# Intsy_128ch_20190417.net
KiCad netlist of a schematic drawn in EAGLE
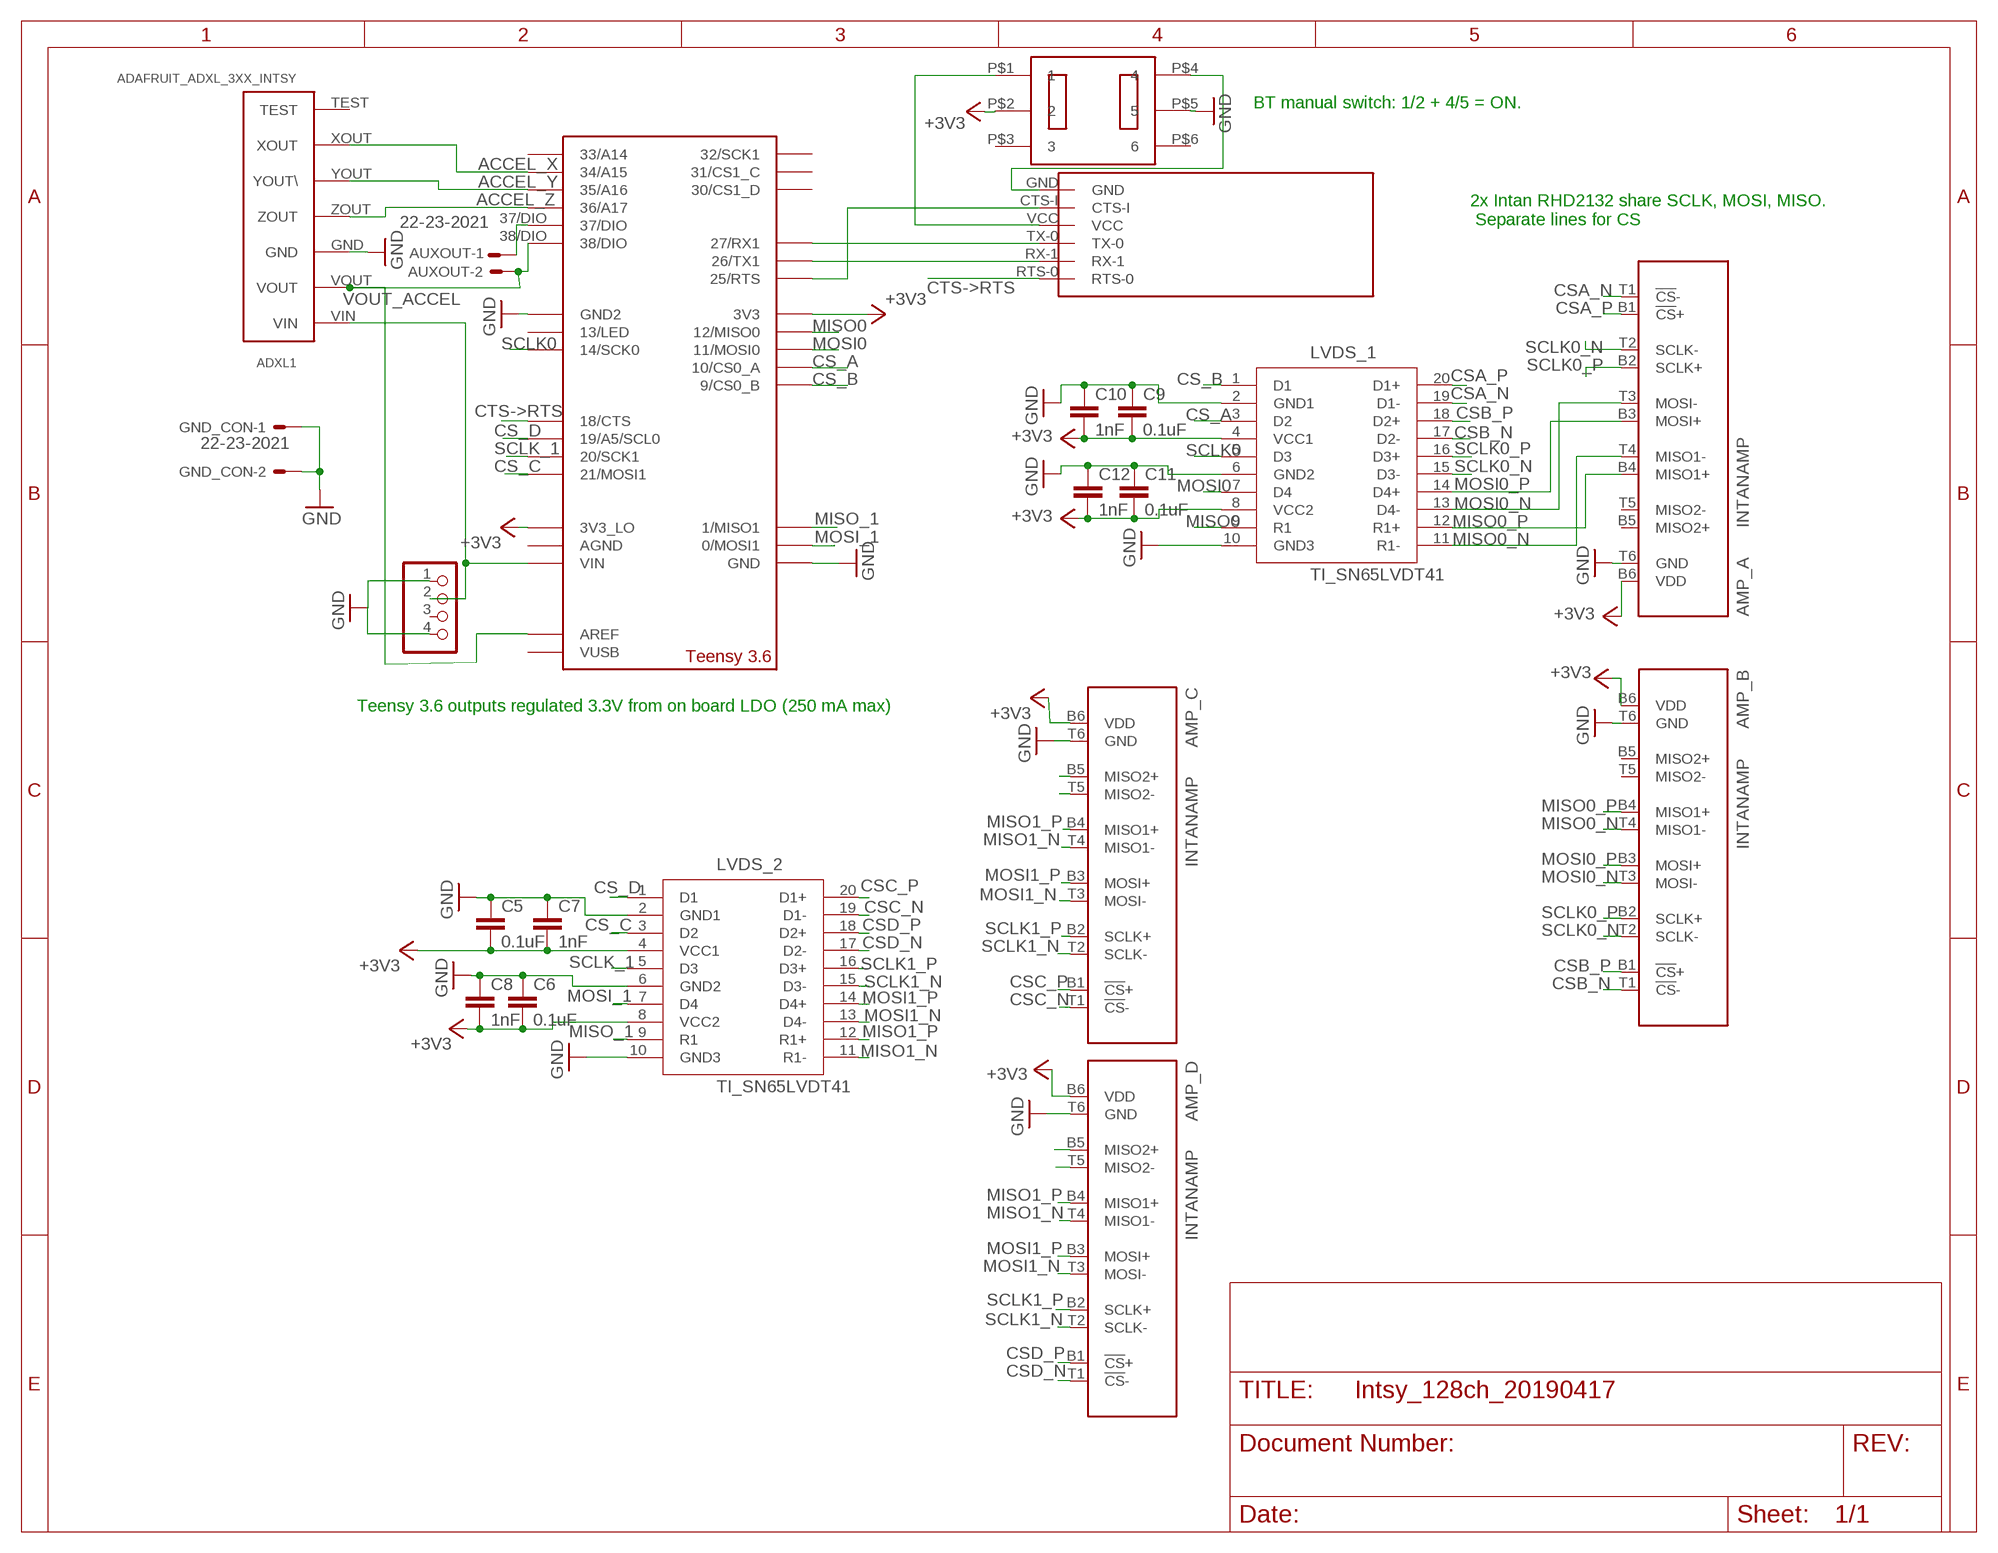
[diagram p0: schematic, sheet 1]

(export (version "E")
  (design (tool "Eeschema 10.0.6"))
  (components
    (comp (ref "ADXL1")
      (value "ADAFRUIT_ADXL_3XX_INTSY")
      (footprint "eagle-import:ADAFRUIT_ADXL_3XX")
      (libsource (lib "eagle-import") (part "ADAFRUIT_ADXL_3XX_INTSY"))
    )
    (comp (ref "AMP_A")
      (value "INTANAMP")
      (footprint "eagle-import:AMPBOARD")
      (libsource (lib "eagle-import") (part "INTANAMP"))
    )
    (comp (ref "AMP_B")
      (value "INTANAMP")
      (footprint "eagle-import:AMPBOARD")
      (libsource (lib "eagle-import") (part "INTANAMP"))
    )
    (comp (ref "AMP_C")
      (value "INTANAMP")
      (footprint "eagle-import:AMPBOARD")
      (libsource (lib "eagle-import") (part "INTANAMP"))
    )
    (comp (ref "AMP_D")
      (value "INTANAMP")
      (footprint "eagle-import:AMPBOARD")
      (libsource (lib "eagle-import") (part "INTANAMP"))
    )
    (comp (ref "AUXOUT")
      (value "22-23-2021")
      (footprint "eagle-import:22-23-2021")
      (fields (field (name "MF") "MOLEX"))
      (libsource (lib "eagle-import") (part "22-23-2021"))
    )
    (comp (ref "C5")
      (value "0.1uF")
      (footprint "eagle-import:C2012")
      (libsource (lib "eagle-import") (part "CC2012"))
    )
    (comp (ref "C6")
      (value "0.1uF")
      (footprint "eagle-import:C2012")
      (libsource (lib "eagle-import") (part "CC2012"))
    )
    (comp (ref "C7")
      (value "1nF")
      (footprint "eagle-import:C2012")
      (libsource (lib "eagle-import") (part "CC2012"))
    )
    (comp (ref "C8")
      (value "1nF")
      (footprint "eagle-import:C2012")
      (libsource (lib "eagle-import") (part "CC2012"))
    )
    (comp (ref "C9")
      (value "0.1uF")
      (footprint "eagle-import:C2012")
      (libsource (lib "eagle-import") (part "CC2012"))
    )
    (comp (ref "C10")
      (value "1nF")
      (footprint "eagle-import:C2012")
      (libsource (lib "eagle-import") (part "CC2012"))
    )
    (comp (ref "C11")
      (value "0.1uF")
      (footprint "eagle-import:C2012")
      (libsource (lib "eagle-import") (part "CC2012"))
    )
    (comp (ref "C12")
      (value "1nF")
      (footprint "eagle-import:C2012")
      (libsource (lib "eagle-import") (part "CC2012"))
    )
    (comp (ref "DPDT_1")
      (value "DPDT_1")
      (footprint "eagle-import:SLIDE_SWITCH_DPDT_NIDEC")
      (libsource (lib "eagle-import") (part "SLIDE_SWITCH_DPDT_NIDEC"))
    )
    (comp (ref "GND_CON")
      (value "22-23-2021")
      (footprint "eagle-import:22-23-2021")
      (fields (field (name "MF") "MOLEX"))
      (libsource (lib "eagle-import") (part "22-23-2021"))
    )
    (comp (ref "LVDS_1")
      (value "TI_SN65LVDT41")
      (footprint "eagle-import:SN65LVDT41_TSSOP20")
      (libsource (lib "eagle-import") (part "TI_SN65LVDT41"))
    )
    (comp (ref "LVDS_2")
      (value "TI_SN65LVDT41")
      (footprint "eagle-import:SN65LVDT41_TSSOP20")
      (libsource (lib "eagle-import") (part "TI_SN65LVDT41"))
    )
    (comp (ref "RN42")
      (value "RN42")
      (footprint "eagle-import:RN42")
      (libsource (lib "eagle-import") (part "RN42"))
    )
    (comp (ref "SW1")
      (value "LiPoIn")
      (footprint "eagle-import:PADS-4")
      (libsource (lib "eagle-import") (part "PADS-4"))
    )
    (comp (ref "U$2")
      (value "TEENSY_3.5/3.6_SIMPLE")
      (footprint "eagle-import:TEENSY_3.5_3.6_SIMPLE")
      (libsource (lib "eagle-import") (part "TEENSY_3.5/3.6_SIMPLE"))
    )
  )
  (nets
    (net (code "1") (name "+3V3") (class "Default")
      (node (ref "AMP_A") (pin "B6") (pinfunction "VDD_B6") (pintype "bidirectional"))
      (node (ref "AMP_B") (pin "B6") (pinfunction "VDD_B6") (pintype "bidirectional"))
      (node (ref "AMP_C") (pin "B6") (pinfunction "VDD_B6") (pintype "bidirectional"))
      (node (ref "AMP_D") (pin "B6") (pinfunction "VDD_B6") (pintype "bidirectional"))
      (node (ref "C10") (pin "2") (pinfunction "2_2") (pintype "passive"))
      (node (ref "C11") (pin "2") (pinfunction "2_2") (pintype "passive"))
      (node (ref "C12") (pin "2") (pinfunction "2_2") (pintype "passive"))
      (node (ref "C5") (pin "2") (pinfunction "2_2") (pintype "passive"))
      (node (ref "C6") (pin "2") (pinfunction "2_2") (pintype "passive"))
      (node (ref "C7") (pin "2") (pinfunction "2_2") (pintype "passive"))
      (node (ref "C8") (pin "2") (pinfunction "2_2") (pintype "passive"))
      (node (ref "C9") (pin "2") (pinfunction "2_2") (pintype "passive"))
      (node (ref "DPDT_1") (pin "P$2") (pinfunction "2_P$2") (pintype "bidirectional"))
      (node (ref "LVDS_1") (pin "4") (pinfunction "VCC1_4") (pintype "power_in"))
      (node (ref "LVDS_1") (pin "8") (pinfunction "VCC2_8") (pintype "bidirectional"))
      (node (ref "LVDS_2") (pin "4") (pinfunction "VCC1_4") (pintype "power_in"))
      (node (ref "LVDS_2") (pin "8") (pinfunction "VCC2_8") (pintype "bidirectional"))
      (node (ref "U$2") (pin "3V3") (pinfunction "3V3_3V3") (pintype "bidirectional"))
      (node (ref "U$2") (pin "3V3_LO") (pinfunction "3V3_LO_3V3_LO") (pintype "bidirectional"))
    )
    (net (code "2") (name "/ACCEL_X") (class "Default")
      (node (ref "ADXL1") (pin "XOUT") (pinfunction "XOUT_XOUT") (pintype "bidirectional"))
      (node (ref "U$2") (pin "34/A15") (pinfunction "34/A15_34/A15") (pintype "input"))
    )
    (net (code "3") (name "/ACCEL_Y") (class "Default")
      (node (ref "ADXL1") (pin "YOUT") (pinfunction "YOUT\\_YOUT") (pintype "bidirectional"))
      (node (ref "U$2") (pin "35/A16") (pinfunction "35/A16_35/A16") (pintype "bidirectional"))
    )
    (net (code "4") (name "/ACCEL_Z") (class "Default")
      (node (ref "ADXL1") (pin "ZOUT") (pinfunction "ZOUT_ZOUT") (pintype "bidirectional"))
      (node (ref "U$2") (pin "36/A17") (pinfunction "36/A17_36/A17") (pintype "bidirectional"))
    )
    (net (code "5") (name "/CSA_N") (class "Default")
      (node (ref "AMP_A") (pin "T1") (pinfunction "~{CS}-_T1") (pintype "bidirectional"))
      (node (ref "LVDS_1") (pin "19") (pinfunction "D1-_19") (pintype "bidirectional"))
    )
    (net (code "6") (name "/CSA_P") (class "Default")
      (node (ref "AMP_A") (pin "B1") (pinfunction "~{CS}+_B1") (pintype "bidirectional"))
      (node (ref "LVDS_1") (pin "20") (pinfunction "D1+_20") (pintype "bidirectional"))
    )
    (net (code "7") (name "/CSB_N") (class "Default")
      (node (ref "AMP_B") (pin "T1") (pinfunction "~{CS}-_T1") (pintype "bidirectional"))
      (node (ref "LVDS_1") (pin "17") (pinfunction "D2-_17") (pintype "bidirectional"))
    )
    (net (code "8") (name "/CSB_P") (class "Default")
      (node (ref "AMP_B") (pin "B1") (pinfunction "~{CS}+_B1") (pintype "bidirectional"))
      (node (ref "LVDS_1") (pin "18") (pinfunction "D2+_18") (pintype "bidirectional"))
    )
    (net (code "9") (name "/CSC_N") (class "Default")
      (node (ref "AMP_C") (pin "T1") (pinfunction "~{CS}-_T1") (pintype "bidirectional"))
      (node (ref "LVDS_2") (pin "19") (pinfunction "D1-_19") (pintype "bidirectional"))
    )
    (net (code "10") (name "/CSC_P") (class "Default")
      (node (ref "AMP_C") (pin "B1") (pinfunction "~{CS}+_B1") (pintype "bidirectional"))
      (node (ref "LVDS_2") (pin "20") (pinfunction "D1+_20") (pintype "bidirectional"))
    )
    (net (code "11") (name "/CSD_N") (class "Default")
      (node (ref "AMP_D") (pin "T1") (pinfunction "~{CS}-_T1") (pintype "bidirectional"))
      (node (ref "LVDS_2") (pin "17") (pinfunction "D2-_17") (pintype "bidirectional"))
    )
    (net (code "12") (name "/CSD_P") (class "Default")
      (node (ref "AMP_D") (pin "B1") (pinfunction "~{CS}+_B1") (pintype "bidirectional"))
      (node (ref "LVDS_2") (pin "18") (pinfunction "D2+_18") (pintype "bidirectional"))
    )
    (net (code "13") (name "/CS_A") (class "Default")
      (node (ref "LVDS_1") (pin "3") (pinfunction "D2_3") (pintype "bidirectional"))
      (node (ref "U$2") (pin "10/CS") (pinfunction "10/CS0_A_10/CS") (pintype "bidirectional"))
    )
    (net (code "14") (name "/CS_B") (class "Default")
      (node (ref "LVDS_1") (pin "1") (pinfunction "D1_1") (pintype "bidirectional"))
      (node (ref "U$2") (pin "9/CS") (pinfunction "9/CS0_B_9/CS") (pintype "bidirectional"))
    )
    (net (code "15") (name "/CS_C") (class "Default")
      (node (ref "LVDS_2") (pin "3") (pinfunction "D2_3") (pintype "bidirectional"))
      (node (ref "U$2") (pin "21/CS0/MOSI1") (pinfunction "21/MOSI1_21/CS0/MOSI1") (pintype "bidirectional"))
    )
    (net (code "16") (name "/CS_D") (class "Default")
      (node (ref "LVDS_2") (pin "1") (pinfunction "D1_1") (pintype "bidirectional"))
      (node (ref "U$2") (pin "19/A5/SCL") (pinfunction "19/A5/SCL0_19/A5/SCL") (pintype "bidirectional"))
    )
    (net (code "17") (name "/CTS->RTS") (class "Default")
      (node (ref "RN42") (pin "RTS-0") (pinfunction "RTS-0_RTS-0") (pintype "bidirectional"))
      (node (ref "U$2") (pin "18/CTS") (pinfunction "18/CTS_18/CTS") (pintype "bidirectional"))
    )
    (net (code "18") (name "/MISO0") (class "Default")
      (node (ref "LVDS_1") (pin "9") (pinfunction "R1_9") (pintype "bidirectional"))
      (node (ref "U$2") (pin "12/MISO0") (pinfunction "12/MISO0_12/MISO0") (pintype "bidirectional"))
    )
    (net (code "19") (name "/MISO0_N") (class "Default")
      (node (ref "AMP_A") (pin "T4") (pinfunction "MISO1-_T4") (pintype "bidirectional"))
      (node (ref "AMP_B") (pin "T4") (pinfunction "MISO1-_T4") (pintype "bidirectional"))
      (node (ref "LVDS_1") (pin "11") (pinfunction "R1-_11") (pintype "bidirectional"))
    )
    (net (code "20") (name "/MISO0_P") (class "Default")
      (node (ref "AMP_A") (pin "B4") (pinfunction "MISO1+_B4") (pintype "bidirectional"))
      (node (ref "AMP_B") (pin "B4") (pinfunction "MISO1+_B4") (pintype "bidirectional"))
      (node (ref "LVDS_1") (pin "12") (pinfunction "R1+_12") (pintype "bidirectional"))
    )
    (net (code "21") (name "/MISO1_N") (class "Default")
      (node (ref "AMP_C") (pin "T4") (pinfunction "MISO1-_T4") (pintype "bidirectional"))
      (node (ref "AMP_D") (pin "T4") (pinfunction "MISO1-_T4") (pintype "bidirectional"))
      (node (ref "LVDS_2") (pin "11") (pinfunction "R1-_11") (pintype "bidirectional"))
    )
    (net (code "22") (name "/MISO1_P") (class "Default")
      (node (ref "AMP_C") (pin "B4") (pinfunction "MISO1+_B4") (pintype "bidirectional"))
      (node (ref "AMP_D") (pin "B4") (pinfunction "MISO1+_B4") (pintype "bidirectional"))
      (node (ref "LVDS_2") (pin "12") (pinfunction "R1+_12") (pintype "bidirectional"))
    )
    (net (code "23") (name "/MISO_1") (class "Default")
      (node (ref "LVDS_2") (pin "9") (pinfunction "R1_9") (pintype "bidirectional"))
      (node (ref "U$2") (pin "1/MISO1") (pinfunction "1/MISO1_1/MISO1") (pintype "bidirectional"))
    )
    (net (code "24") (name "/MOSI0") (class "Default")
      (node (ref "LVDS_1") (pin "7") (pinfunction "D4_7") (pintype "bidirectional"))
      (node (ref "U$2") (pin "11/MOSI0") (pinfunction "11/MOSI0_11/MOSI0") (pintype "bidirectional"))
    )
    (net (code "25") (name "/MOSI0_N") (class "Default")
      (node (ref "AMP_A") (pin "T3") (pinfunction "MOSI-_T3") (pintype "bidirectional"))
      (node (ref "AMP_B") (pin "T3") (pinfunction "MOSI-_T3") (pintype "bidirectional"))
      (node (ref "LVDS_1") (pin "13") (pinfunction "D4-_13") (pintype "bidirectional"))
    )
    (net (code "26") (name "/MOSI0_P") (class "Default")
      (node (ref "AMP_A") (pin "B3") (pinfunction "MOSI+_B3") (pintype "bidirectional"))
      (node (ref "AMP_B") (pin "B3") (pinfunction "MOSI+_B3") (pintype "bidirectional"))
      (node (ref "LVDS_1") (pin "14") (pinfunction "D4+_14") (pintype "bidirectional"))
    )
    (net (code "27") (name "/MOSI1_N") (class "Default")
      (node (ref "AMP_C") (pin "T3") (pinfunction "MOSI-_T3") (pintype "bidirectional"))
      (node (ref "AMP_D") (pin "T3") (pinfunction "MOSI-_T3") (pintype "bidirectional"))
      (node (ref "LVDS_2") (pin "13") (pinfunction "D4-_13") (pintype "bidirectional"))
    )
    (net (code "28") (name "/MOSI1_P") (class "Default")
      (node (ref "AMP_C") (pin "B3") (pinfunction "MOSI+_B3") (pintype "bidirectional"))
      (node (ref "AMP_D") (pin "B3") (pinfunction "MOSI+_B3") (pintype "bidirectional"))
      (node (ref "LVDS_2") (pin "14") (pinfunction "D4+_14") (pintype "bidirectional"))
    )
    (net (code "29") (name "/MOSI_1") (class "Default")
      (node (ref "LVDS_2") (pin "7") (pinfunction "D4_7") (pintype "bidirectional"))
      (node (ref "U$2") (pin "0/MOSI1") (pinfunction "0/MOSI1_0/MOSI1") (pintype "bidirectional"))
    )
    (net (code "30") (name "/SCLK0") (class "Default")
      (node (ref "LVDS_1") (pin "5") (pinfunction "D3_5") (pintype "bidirectional"))
      (node (ref "U$2") (pin "14/SCK0") (pinfunction "14/SCK0_14/SCK0") (pintype "bidirectional"))
    )
    (net (code "31") (name "/SCLK0_N") (class "Default")
      (node (ref "AMP_A") (pin "T2") (pinfunction "SCLK-_T2") (pintype "bidirectional"))
      (node (ref "AMP_B") (pin "T2") (pinfunction "SCLK-_T2") (pintype "bidirectional"))
      (node (ref "LVDS_1") (pin "15") (pinfunction "D3-_15") (pintype "bidirectional"))
    )
    (net (code "32") (name "/SCLK0_P") (class "Default")
      (node (ref "AMP_A") (pin "B2") (pinfunction "SCLK+_B2") (pintype "bidirectional"))
      (node (ref "AMP_B") (pin "B2") (pinfunction "SCLK+_B2") (pintype "bidirectional"))
      (node (ref "LVDS_1") (pin "16") (pinfunction "D3+_16") (pintype "bidirectional"))
    )
    (net (code "33") (name "/SCLK1_N") (class "Default")
      (node (ref "AMP_C") (pin "T2") (pinfunction "SCLK-_T2") (pintype "bidirectional"))
      (node (ref "AMP_D") (pin "T2") (pinfunction "SCLK-_T2") (pintype "bidirectional"))
      (node (ref "LVDS_2") (pin "15") (pinfunction "D3-_15") (pintype "bidirectional"))
    )
    (net (code "34") (name "/SCLK1_P") (class "Default")
      (node (ref "AMP_C") (pin "B2") (pinfunction "SCLK+_B2") (pintype "bidirectional"))
      (node (ref "AMP_D") (pin "B2") (pinfunction "SCLK+_B2") (pintype "bidirectional"))
      (node (ref "LVDS_2") (pin "16") (pinfunction "D3+_16") (pintype "bidirectional"))
    )
    (net (code "35") (name "/SCLK_1") (class "Default")
      (node (ref "LVDS_2") (pin "5") (pinfunction "D3_5") (pintype "bidirectional"))
      (node (ref "U$2") (pin "20/CS0/SCK1") (pinfunction "20/SCK1_20/CS0/SCK1") (pintype "bidirectional"))
    )
    (net (code "36") (name "/VOUT_ACCEL") (class "Default")
      (node (ref "ADXL1") (pin "VOUT") (pinfunction "VOUT_VOUT") (pintype "bidirectional"))
      (node (ref "AUXOUT") (pin "2") (pinfunction "S_2") (pintype "passive"))
      (node (ref "U$2") (pin "38/DIO") (pinfunction "38/DIO_38/DIO") (pintype "bidirectional"))
      (node (ref "U$2") (pin "AREF") (pinfunction "AREF_AREF") (pintype "bidirectional"))
    )
    (net (code "37") (name "GND") (class "Default")
      (node (ref "ADXL1") (pin "GND") (pinfunction "GND_GND") (pintype "power_in"))
      (node (ref "AMP_A") (pin "T6") (pinfunction "GND_T6") (pintype "power_in"))
      (node (ref "AMP_B") (pin "T6") (pinfunction "GND_T6") (pintype "power_in"))
      (node (ref "AMP_C") (pin "T6") (pinfunction "GND_T6") (pintype "power_in"))
      (node (ref "AMP_D") (pin "T6") (pinfunction "GND_T6") (pintype "power_in"))
      (node (ref "C10") (pin "1") (pinfunction "1_1") (pintype "passive"))
      (node (ref "C11") (pin "1") (pinfunction "1_1") (pintype "passive"))
      (node (ref "C12") (pin "1") (pinfunction "1_1") (pintype "passive"))
      (node (ref "C5") (pin "1") (pinfunction "1_1") (pintype "passive"))
      (node (ref "C6") (pin "1") (pinfunction "1_1") (pintype "passive"))
      (node (ref "C7") (pin "1") (pinfunction "1_1") (pintype "passive"))
      (node (ref "C8") (pin "1") (pinfunction "1_1") (pintype "passive"))
      (node (ref "C9") (pin "1") (pinfunction "1_1") (pintype "passive"))
      (node (ref "DPDT_1") (pin "P$5") (pinfunction "5_P$5") (pintype "bidirectional"))
      (node (ref "GND_CON") (pin "1") (pinfunction "S_1") (pintype "passive"))
      (node (ref "GND_CON") (pin "2") (pinfunction "S_2") (pintype "passive"))
      (node (ref "LVDS_1") (pin "10") (pinfunction "GND3_10") (pintype "power_in"))
      (node (ref "LVDS_1") (pin "2") (pinfunction "GND1_2") (pintype "power_in"))
      (node (ref "LVDS_1") (pin "6") (pinfunction "GND2_6") (pintype "power_in"))
      (node (ref "LVDS_2") (pin "10") (pinfunction "GND3_10") (pintype "power_in"))
      (node (ref "LVDS_2") (pin "2") (pinfunction "GND1_2") (pintype "power_in"))
      (node (ref "LVDS_2") (pin "6") (pinfunction "GND2_6") (pintype "power_in"))
      (node (ref "SW1") (pin "1") (pinfunction "1_1") (pintype "passive"))
      (node (ref "SW1") (pin "4") (pinfunction "4_4") (pintype "passive"))
      (node (ref "U$2") (pin "GND") (pinfunction "GND_GND") (pintype "bidirectional"))
      (node (ref "U$2") (pin "GND2") (pinfunction "GND2_GND2") (pintype "bidirectional"))
    )
    (net (code "38") (name "Net-(ADXL1-PadVIN)") (class "Default")
      (node (ref "ADXL1") (pin "VIN") (pinfunction "VIN_VIN") (pintype "power_in"))
      (node (ref "SW1") (pin "2") (pinfunction "2_2") (pintype "passive"))
      (node (ref "U$2") (pin "VIN") (pinfunction "VIN_VIN") (pintype "bidirectional"))
    )
    (net (code "39") (name "Net-(AUXOUTA-S)") (class "Default")
      (node (ref "AUXOUT") (pin "1") (pinfunction "S_1") (pintype "passive"))
      (node (ref "U$2") (pin "37/DIO") (pinfunction "37/DIO_37/DIO") (pintype "bidirectional"))
    )
    (net (code "40") (name "Net-(DPDT_1-1)") (class "Default")
      (node (ref "DPDT_1") (pin "P$1") (pinfunction "1_P$1") (pintype "bidirectional"))
      (node (ref "RN42") (pin "VCC") (pinfunction "VCC_VCC") (pintype "bidirectional"))
    )
    (net (code "41") (name "Net-(DPDT_1-4)") (class "Default")
      (node (ref "DPDT_1") (pin "P$4") (pinfunction "4_P$4") (pintype "bidirectional"))
      (node (ref "RN42") (pin "GND") (pinfunction "GND_GND") (pintype "bidirectional"))
    )
    (net (code "42") (name "Net-(RN42-PadCTS-I)") (class "Default")
      (node (ref "RN42") (pin "CTS-I") (pinfunction "CTS-I_CTS-I") (pintype "bidirectional"))
      (node (ref "U$2") (pin "25/RTS") (pinfunction "25/RTS_25/RTS") (pintype "bidirectional"))
    )
    (net (code "43") (name "Net-(RN42-PadRX-1)") (class "Default")
      (node (ref "RN42") (pin "RX-1") (pinfunction "RX-1_RX-1") (pintype "bidirectional"))
      (node (ref "U$2") (pin "26/TX1") (pinfunction "26/TX1_26/TX1") (pintype "bidirectional"))
    )
    (net (code "44") (name "Net-(RN42-PadTX-0)") (class "Default")
      (node (ref "RN42") (pin "TX-0") (pinfunction "TX-0_TX-0") (pintype "bidirectional"))
      (node (ref "U$2") (pin "27/RX1") (pinfunction "27/RX1_27/RX1") (pintype "bidirectional"))
    )
    (net (code "45") (name "unconnected-(ADXL1-PadTEST)") (class "Default")
      (node (ref "ADXL1") (pin "TEST") (pinfunction "TEST_TEST") (pintype "no_connect"))
    )
    (net (code "46") (name "unconnected-(AMP_A-MISO2+-PadB5)") (class "Default")
      (node (ref "AMP_A") (pin "B5") (pinfunction "MISO2+_B5") (pintype "bidirectional"))
    )
    (net (code "47") (name "unconnected-(AMP_A-MISO2--PadT5)") (class "Default")
      (node (ref "AMP_A") (pin "T5") (pinfunction "MISO2-_T5") (pintype "bidirectional"))
    )
    (net (code "48") (name "unconnected-(AMP_B-MISO2+-PadB5)") (class "Default")
      (node (ref "AMP_B") (pin "B5") (pinfunction "MISO2+_B5") (pintype "bidirectional"))
    )
    (net (code "49") (name "unconnected-(AMP_B-MISO2--PadT5)") (class "Default")
      (node (ref "AMP_B") (pin "T5") (pinfunction "MISO2-_T5") (pintype "bidirectional"))
    )
    (net (code "50") (name "unconnected-(AMP_C-MISO2+-PadB5)") (class "Default")
      (node (ref "AMP_C") (pin "B5") (pinfunction "MISO2+_B5") (pintype "bidirectional"))
    )
    (net (code "51") (name "unconnected-(AMP_C-MISO2--PadT5)") (class "Default")
      (node (ref "AMP_C") (pin "T5") (pinfunction "MISO2-_T5") (pintype "bidirectional"))
    )
    (net (code "52") (name "unconnected-(AMP_D-MISO2+-PadB5)") (class "Default")
      (node (ref "AMP_D") (pin "B5") (pinfunction "MISO2+_B5") (pintype "bidirectional"))
    )
    (net (code "53") (name "unconnected-(AMP_D-MISO2--PadT5)") (class "Default")
      (node (ref "AMP_D") (pin "T5") (pinfunction "MISO2-_T5") (pintype "bidirectional"))
    )
    (net (code "54") (name "unconnected-(DPDT_1-3-PadP$3)") (class "Default")
      (node (ref "DPDT_1") (pin "P$3") (pinfunction "3_P$3") (pintype "bidirectional"))
    )
    (net (code "55") (name "unconnected-(DPDT_1-6-PadP$6)") (class "Default")
      (node (ref "DPDT_1") (pin "P$6") (pinfunction "6_P$6") (pintype "bidirectional"))
    )
    (net (code "56") (name "unconnected-(SW1-Pad3)") (class "Default")
      (node (ref "SW1") (pin "3") (pinfunction "3_3") (pintype "passive"))
    )
    (net (code "57") (name "unconnected-(U$2-13{slash}LED-Pad13{slash}LED{slash}SCK0)") (class "Default")
      (node (ref "U$2") (pin "13/LED/SCK0") (pinfunction "13/LED_13/LED/SCK0") (pintype "bidirectional"))
    )
    (net (code "58") (name "unconnected-(U$2-30{slash}CS1_D-Pad30{slash}CS1)") (class "Default")
      (node (ref "U$2") (pin "30/CS1") (pinfunction "30/CS1_D_30/CS1") (pintype "bidirectional"))
    )
    (net (code "59") (name "unconnected-(U$2-31{slash}CS1_C-Pad31{slash}CS1)") (class "Default")
      (node (ref "U$2") (pin "31/CS1") (pinfunction "31/CS1_C_31/CS1") (pintype "bidirectional"))
    )
    (net (code "60") (name "unconnected-(U$2-Pad32{slash}SCK1)") (class "Default")
      (node (ref "U$2") (pin "32/SCK1") (pinfunction "32/SCK1_32/SCK1") (pintype "bidirectional"))
    )
    (net (code "61") (name "unconnected-(U$2-Pad33{slash}A14)") (class "Default")
      (node (ref "U$2") (pin "33/A14") (pinfunction "33/A14_33/A14") (pintype "bidirectional"))
    )
    (net (code "62") (name "unconnected-(U$2-PadAGND)") (class "Default")
      (node (ref "U$2") (pin "AGND") (pinfunction "AGND_AGND") (pintype "bidirectional"))
    )
    (net (code "63") (name "unconnected-(U$2-PadVUSB)") (class "Default")
      (node (ref "U$2") (pin "VUSB") (pinfunction "VUSB_VUSB") (pintype "bidirectional"))
    )
  )
)
